# Nestling_2_1_EXB_POWER.net
KiCad netlist of a schematic drawn in Altium Designer
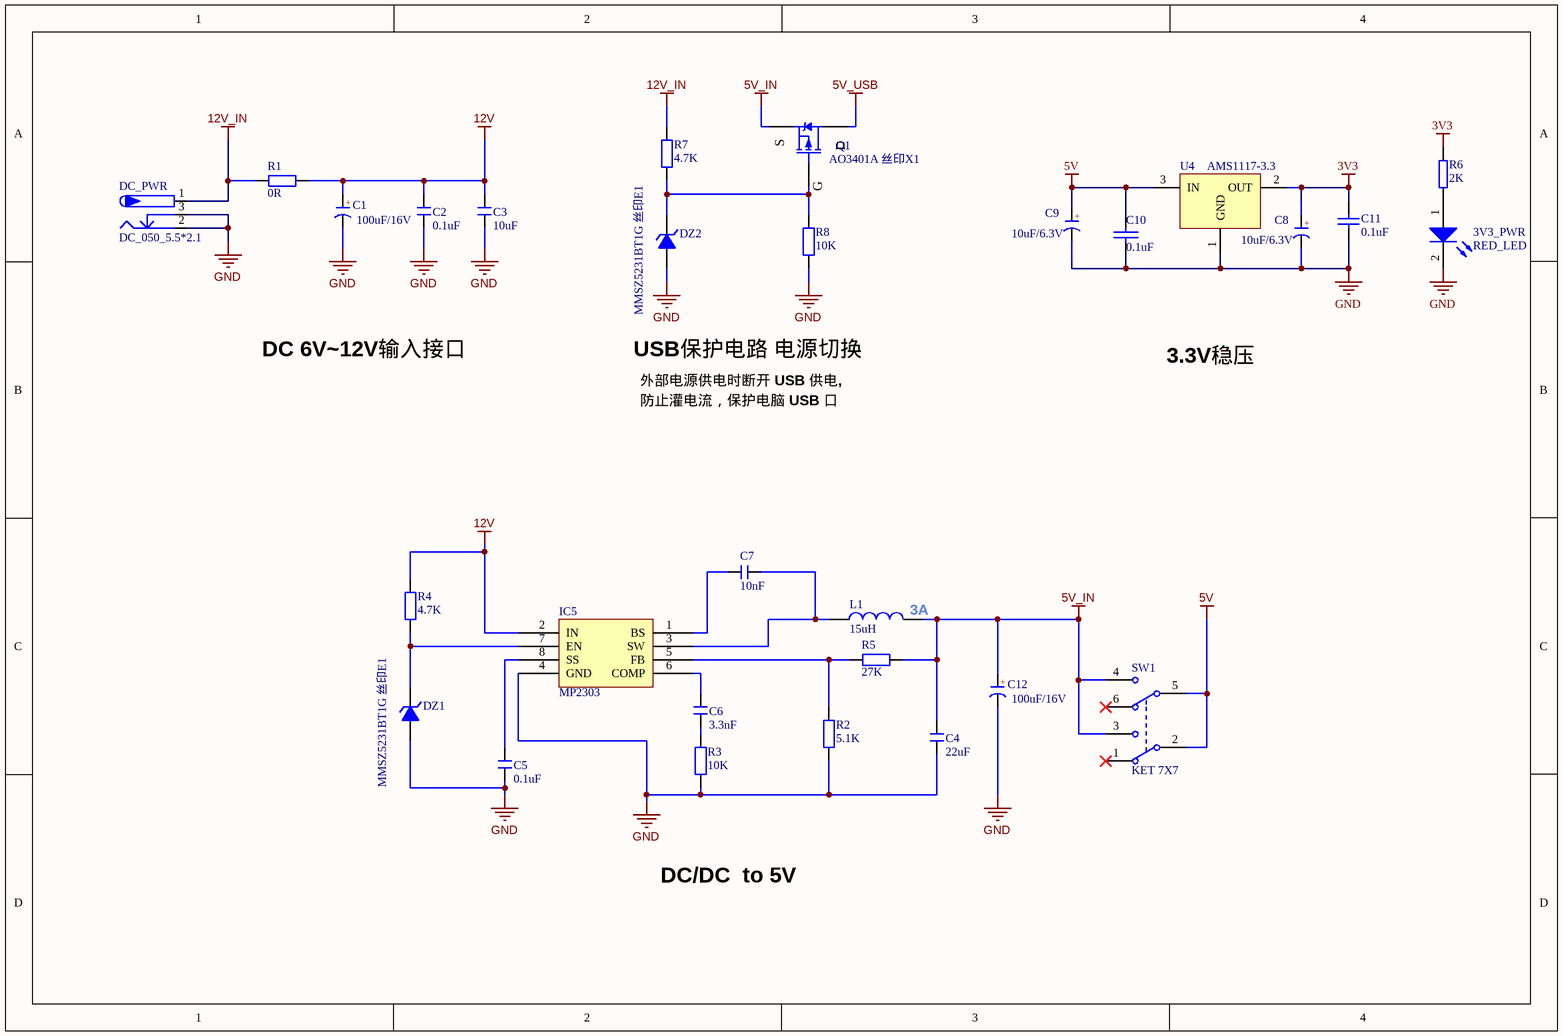
[diagram p0: Nestling_2.1_EXB_POWER.SchDoc]

(export (version "E")
  (design (tool "Eeschema 10.0.6"))
  (components
    (comp (ref "3V3_PWR")
      (value "RED_LED")
      (footprint "LED 0603R")
      (description "Typical INFRARED GaAs LED")
      (libsource (lib "Miscellaneous Devices") (part "LED0"))
    )
    (comp (ref "C1")
      (value "100uF/16V")
      (footprint "CM D(6.3*5.4)")
      (description "贴片电解电容")
      (fields (field (name "版权归属") "源创客"))
      (libsource (lib "altium-import") (part "root_3_C-CM_"))
    )
    (comp (ref "C2")
      (value "0.1uF")
      (footprint "C 0603_M")
      (description "无极性贴片电容")
      (fields (field (name "版权归属") "源创客"))
      (libsource (lib "altium-import") (part "root_1_C_"))
    )
    (comp (ref "C3")
      (value "10uF")
      (footprint "C 0603_M")
      (description "无极性贴片电容")
      (fields (field (name "版权归属") "源创客"))
      (libsource (lib "altium-import") (part "root_1_C_"))
    )
    (comp (ref "C4")
      (value "22uF")
      (footprint "C 0603_M")
      (description "无极性贴片电容")
      (fields (field (name "版权归属") "源创客"))
      (libsource (lib "altium-import") (part "root_1_C_"))
    )
    (comp (ref "C5")
      (value "0.1uF")
      (footprint "C 0603_M")
      (description "无极性贴片电容")
      (fields (field (name "版权归属") "源创客"))
      (libsource (lib "altium-import") (part "root_1_C_"))
    )
    (comp (ref "C6")
      (value "3.3nF")
      (footprint "C 0603_M")
      (description "无极性贴片电容")
      (fields (field (name "版权归属") "源创客"))
      (libsource (lib "altium-import") (part "root_1_C_"))
    )
    (comp (ref "C7")
      (value "10nF")
      (footprint "C 0603_M")
      (description "无极性贴片电容")
      (fields (field (name "版权归属") "源创客"))
      (libsource (lib "altium-import") (part "root_2_C_"))
    )
    (comp (ref "C8")
      (value "10uF/6.3V")
      (footprint "CD S(2012)")
      (description "贴片钽电容")
      (fields (field (name "版权归属") "源创客"))
      (libsource (lib "altium-import") (part "root_3_C-CD_"))
    )
    (comp (ref "C9")
      (value "10uF/6.3V")
      (footprint "CD S(2012)")
      (description "贴片钽电容")
      (fields (field (name "版权归属") "源创客"))
      (libsource (lib "altium-import") (part "root_3_C-CD_"))
    )
    (comp (ref "C10")
      (value "0.1uF")
      (footprint "C 0603_M")
      (description "Capacitor")
      (libsource (lib "*") (part "CAP"))
    )
    (comp (ref "C11")
      (value "0.1uF")
      (footprint "C 0603_M")
      (description "Capacitor")
      (fields (field (name "PUBLISHER") "Altium Limited"))
      (libsource (lib "*") (part "Cap"))
    )
    (comp (ref "C12")
      (value "100uF/16V")
      (footprint "CM D(6.3*5.4)")
      (description "贴片电解电容")
      (fields (field (name "版权归属") "源创客"))
      (libsource (lib "altium-import") (part "root_3_C-CM_"))
    )
    (comp (ref "DC_PWR")
      (value "DC_050_5.5*2.1")
      (footprint "DC-050")
      (description "低压电源接口")
      (fields (field (name "版权归属") "源创客"))
      (libsource (lib "altium-import") (part "root_0_mirrored_P-DC_"))
    )
    (comp (ref "DZ1")
      (value "MMSZ5231BT1G 丝印E1")
      (footprint "SOD-123")
      (description "5.1V/0.5W稳压管")
      (fields (field (name "版权归属") "源创客"))
      (libsource (lib "altium-import") (part "root_0_1N4625_"))
    )
    (comp (ref "DZ2")
      (value "MMSZ5231BT1G 丝印E1")
      (footprint "SOD-123")
      (description "5.1V/0.5W稳压管")
      (fields (field (name "版权归属") "源创客"))
      (libsource (lib "altium-import") (part "root_0_1N4625_"))
    )
    (comp (ref "IC5")
      (value "MP2303")
      (footprint "SOP8_N")
      (libsource (lib "altium-import") (part "root_0_MP2303_"))
    )
    (comp (ref "L1")
      (value "15uH")
      (footprint "L-SMD-0630")
      (description "小功率贴片电感")
      (fields (field (name "版权归属") "源创客"))
      (libsource (lib "3.1   - 电阻-电容-电感") (part "L"))
    )
    (comp (ref "Q1")
      (value "AO3401A 丝印X1")
      (footprint "SOT23-3N")
      (description "P沟道场效应管")
      (fields (field (name "版权归属") "源创客"))
      (libsource (lib "altium-import") (part "root_1_mirrored_SI2301_"))
    )
    (comp (ref "R1")
      (value "0R")
      (footprint "R 0603_M")
      (description "贴片电阻")
      (fields (field (name "版权归属") "源创客"))
      (libsource (lib "altium-import") (part "root_0_R_"))
    )
    (comp (ref "R2")
      (value "5.1K")
      (footprint "R 0603_M")
      (description "贴片电阻")
      (fields (field (name "版权归属") "源创客"))
      (libsource (lib "altium-import") (part "root_1_R_"))
    )
    (comp (ref "R3")
      (value "10K")
      (footprint "R 0603_M")
      (description "贴片电阻")
      (fields (field (name "版权归属") "源创客"))
      (libsource (lib "altium-import") (part "root_1_R_"))
    )
    (comp (ref "R4")
      (value "4.7K")
      (footprint "R 0603_M")
      (description "贴片电阻")
      (fields (field (name "版权归属") "源创客"))
      (libsource (lib "altium-import") (part "root_1_R_"))
    )
    (comp (ref "R5")
      (value "27K")
      (footprint "R 0603_M")
      (description "贴片电阻")
      (fields (field (name "版权归属") "源创客"))
      (libsource (lib "altium-import") (part "root_2_R_"))
    )
    (comp (ref "R6") (value "2K") (footprint "R 0603_M") (libsource (lib "ZIBO V2.0_Main") (part "R")))
    (comp (ref "R7")
      (value "4.7K")
      (footprint "R 0603_M")
      (description "贴片电阻")
      (fields (field (name "版权归属") "源创客"))
      (libsource (lib "altium-import") (part "root_1_R_"))
    )
    (comp (ref "R8")
      (value "10K")
      (footprint "R 0603_M")
      (description "贴片电阻")
      (fields (field (name "版权归属") "源创客"))
      (libsource (lib "altium-import") (part "root_1_R_"))
    )
    (comp (ref "SW1")
      (value "KET 7X7")
      (footprint "KFT DIP-7X7")
      (description "7*7自锁开关")
      (fields (field (name "版权归属") "源创客"))
      (libsource (lib "altium-import") (part "root_2_KET 7X7_"))
    )
    (comp (ref "U4")
      (value "AMS1117-3.3")
      (footprint "SOT223_N")
      (libsource (lib "Newcapec9263_Board_NEW") (part "LT1085CM-3.3"))
    )
  )
  (nets
    (net (code "1") (name "3V3") (class "Default")
      (node (ref "C11") (pin "1") (pinfunction "1_1") (pintype "passive"))
      (node (ref "C8") (pin "1") (pinfunction "A_1") (pintype "passive"))
      (node (ref "R6") (pin "2") (pinfunction "2_2") (pintype "passive"))
      (node (ref "U4") (pin "2") (pinfunction "OUT_2") (pintype "passive"))
    )
    (net (code "2") (name "5V") (class "Default")
      (node (ref "C10") (pin "1") (pinfunction "1_1") (pintype "passive"))
      (node (ref "C9") (pin "1") (pinfunction "A_1") (pintype "passive"))
      (node (ref "SW1") (pin "2") (pinfunction "COM2_2") (pintype "passive"))
      (node (ref "SW1") (pin "5") (pinfunction "COM2_5") (pintype "passive"))
      (node (ref "U4") (pin "3") (pinfunction "IN_3") (pintype "passive"))
    )
    (net (code "3") (name "5V_IN") (class "Default")
      (node (ref "C12") (pin "1") (pinfunction "A_1") (pintype "passive"))
      (node (ref "C4") (pin "2") (pinfunction "2_2") (pintype "passive"))
      (node (ref "L1") (pin "2") (pinfunction "2_2") (pintype "passive"))
      (node (ref "Q1") (pin "2") (pinfunction "S_2") (pintype "passive"))
      (node (ref "R5") (pin "1") (pinfunction "1_1") (pintype "passive"))
      (node (ref "SW1") (pin "3") (pinfunction "NO1_3") (pintype "passive"))
      (node (ref "SW1") (pin "4") (pinfunction "NO2_4") (pintype "passive"))
    )
    (net (code "4") (name "5V_USB") (class "Default")
      (node (ref "Q1") (pin "3") (pinfunction "D_3") (pintype "passive"))
    )
    (net (code "5") (name "12V") (class "Default")
      (node (ref "C1") (pin "1") (pinfunction "A_1") (pintype "passive"))
      (node (ref "C2") (pin "2") (pinfunction "2_2") (pintype "passive"))
      (node (ref "C3") (pin "2") (pinfunction "2_2") (pintype "passive"))
      (node (ref "IC5") (pin "2") (pinfunction "IN_2") (pintype "passive"))
      (node (ref "R1") (pin "2") (pinfunction "2_2") (pintype "passive"))
      (node (ref "R4") (pin "2") (pinfunction "2_2") (pintype "passive"))
    )
    (net (code "6") (name "12V_IN") (class "Default")
      (node (ref "DC_PWR") (pin "1") (pintype "power_in"))
      (node (ref "R1") (pin "1") (pinfunction "1_1") (pintype "passive"))
      (node (ref "R7") (pin "2") (pinfunction "2_2") (pintype "passive"))
    )
    (net (code "7") (name "GND") (class "Default")
      (node (ref "3V3_PWR") (pin "2") (pinfunction "K_2") (pintype "passive"))
      (node (ref "C1") (pin "2") (pinfunction "K_2") (pintype "passive"))
      (node (ref "C10") (pin "2") (pinfunction "2_2") (pintype "passive"))
      (node (ref "C11") (pin "2") (pinfunction "2_2") (pintype "passive"))
      (node (ref "C12") (pin "2") (pinfunction "K_2") (pintype "passive"))
      (node (ref "C2") (pin "1") (pinfunction "1_1") (pintype "passive"))
      (node (ref "C3") (pin "1") (pinfunction "1_1") (pintype "passive"))
      (node (ref "C4") (pin "1") (pinfunction "1_1") (pintype "passive"))
      (node (ref "C5") (pin "1") (pinfunction "1_1") (pintype "passive"))
      (node (ref "C8") (pin "2") (pinfunction "K_2") (pintype "passive"))
      (node (ref "C9") (pin "2") (pinfunction "K_2") (pintype "passive"))
      (node (ref "DC_PWR") (pin "2") (pintype "power_in"))
      (node (ref "DC_PWR") (pin "3") (pintype "power_in"))
      (node (ref "DZ1") (pin "1") (pinfunction "A_1") (pintype "passive"))
      (node (ref "DZ2") (pin "1") (pinfunction "A_1") (pintype "passive"))
      (node (ref "IC5") (pin "4") (pinfunction "GND_4") (pintype "passive"))
      (node (ref "R2") (pin "1") (pinfunction "1_1") (pintype "passive"))
      (node (ref "R3") (pin "1") (pinfunction "1_1") (pintype "passive"))
      (node (ref "R8") (pin "1") (pinfunction "1_1") (pintype "passive"))
      (node (ref "U4") (pin "1") (pinfunction "GND_1") (pintype "passive"))
    )
    (net (code "8") (name "Net-(3V3_PWR-A)") (class "Default")
      (node (ref "3V3_PWR") (pin "1") (pinfunction "A_1") (pintype "passive"))
      (node (ref "R6") (pin "1") (pinfunction "1_1") (pintype "passive"))
    )
    (net (code "9") (name "Net-(C6-Pad1)") (class "Default")
      (node (ref "C6") (pin "1") (pinfunction "1_1") (pintype "passive"))
      (node (ref "R3") (pin "2") (pinfunction "2_2") (pintype "passive"))
    )
    (net (code "10") (name "Net-(DZ1-K)") (class "Default")
      (node (ref "DZ1") (pin "2") (pinfunction "K_2") (pintype "passive"))
      (node (ref "IC5") (pin "7") (pinfunction "EN_7") (pintype "passive"))
      (node (ref "R4") (pin "1") (pinfunction "1_1") (pintype "passive"))
    )
    (net (code "11") (name "Net-(DZ2-K)") (class "Default")
      (node (ref "DZ2") (pin "2") (pinfunction "K_2") (pintype "passive"))
      (node (ref "Q1") (pin "1") (pinfunction "G_1") (pintype "passive"))
      (node (ref "R7") (pin "1") (pinfunction "1_1") (pintype "passive"))
      (node (ref "R8") (pin "2") (pinfunction "2_2") (pintype "passive"))
    )
    (net (code "12") (name "Net-(IC5-BS)") (class "Default")
      (node (ref "C7") (pin "2") (pinfunction "2_2") (pintype "passive"))
      (node (ref "IC5") (pin "1") (pinfunction "BS_1") (pintype "passive"))
    )
    (net (code "13") (name "Net-(IC5-COMP)") (class "Default")
      (node (ref "C6") (pin "2") (pinfunction "2_2") (pintype "passive"))
      (node (ref "IC5") (pin "6") (pinfunction "COMP_6") (pintype "passive"))
    )
    (net (code "14") (name "Net-(IC5-FB)") (class "Default")
      (node (ref "IC5") (pin "5") (pinfunction "FB_5") (pintype "passive"))
      (node (ref "R2") (pin "2") (pinfunction "2_2") (pintype "passive"))
      (node (ref "R5") (pin "2") (pinfunction "2_2") (pintype "passive"))
    )
    (net (code "15") (name "Net-(IC5-SS)") (class "Default")
      (node (ref "C5") (pin "2") (pinfunction "2_2") (pintype "passive"))
      (node (ref "IC5") (pin "8") (pinfunction "SS_8") (pintype "passive"))
    )
    (net (code "16") (name "Net-(IC5-SW)") (class "Default")
      (node (ref "C7") (pin "1") (pinfunction "1_1") (pintype "passive"))
      (node (ref "IC5") (pin "3") (pinfunction "SW_3") (pintype "passive"))
      (node (ref "L1") (pin "1") (pinfunction "1_1") (pintype "passive"))
    )
    (net (code "17") (name "unconnected-(SW1-NC1-Pad1)") (class "Default")
      (node (ref "SW1") (pin "1") (pinfunction "NC1_1") (pintype "passive+no_connect"))
    )
    (net (code "18") (name "unconnected-(SW1-NC2-Pad6)") (class "Default")
      (node (ref "SW1") (pin "6") (pinfunction "NC2_6") (pintype "passive+no_connect"))
    )
  )
)
